# SDP_2.net
KiCad netlist of a schematic drawn in Altium Designer
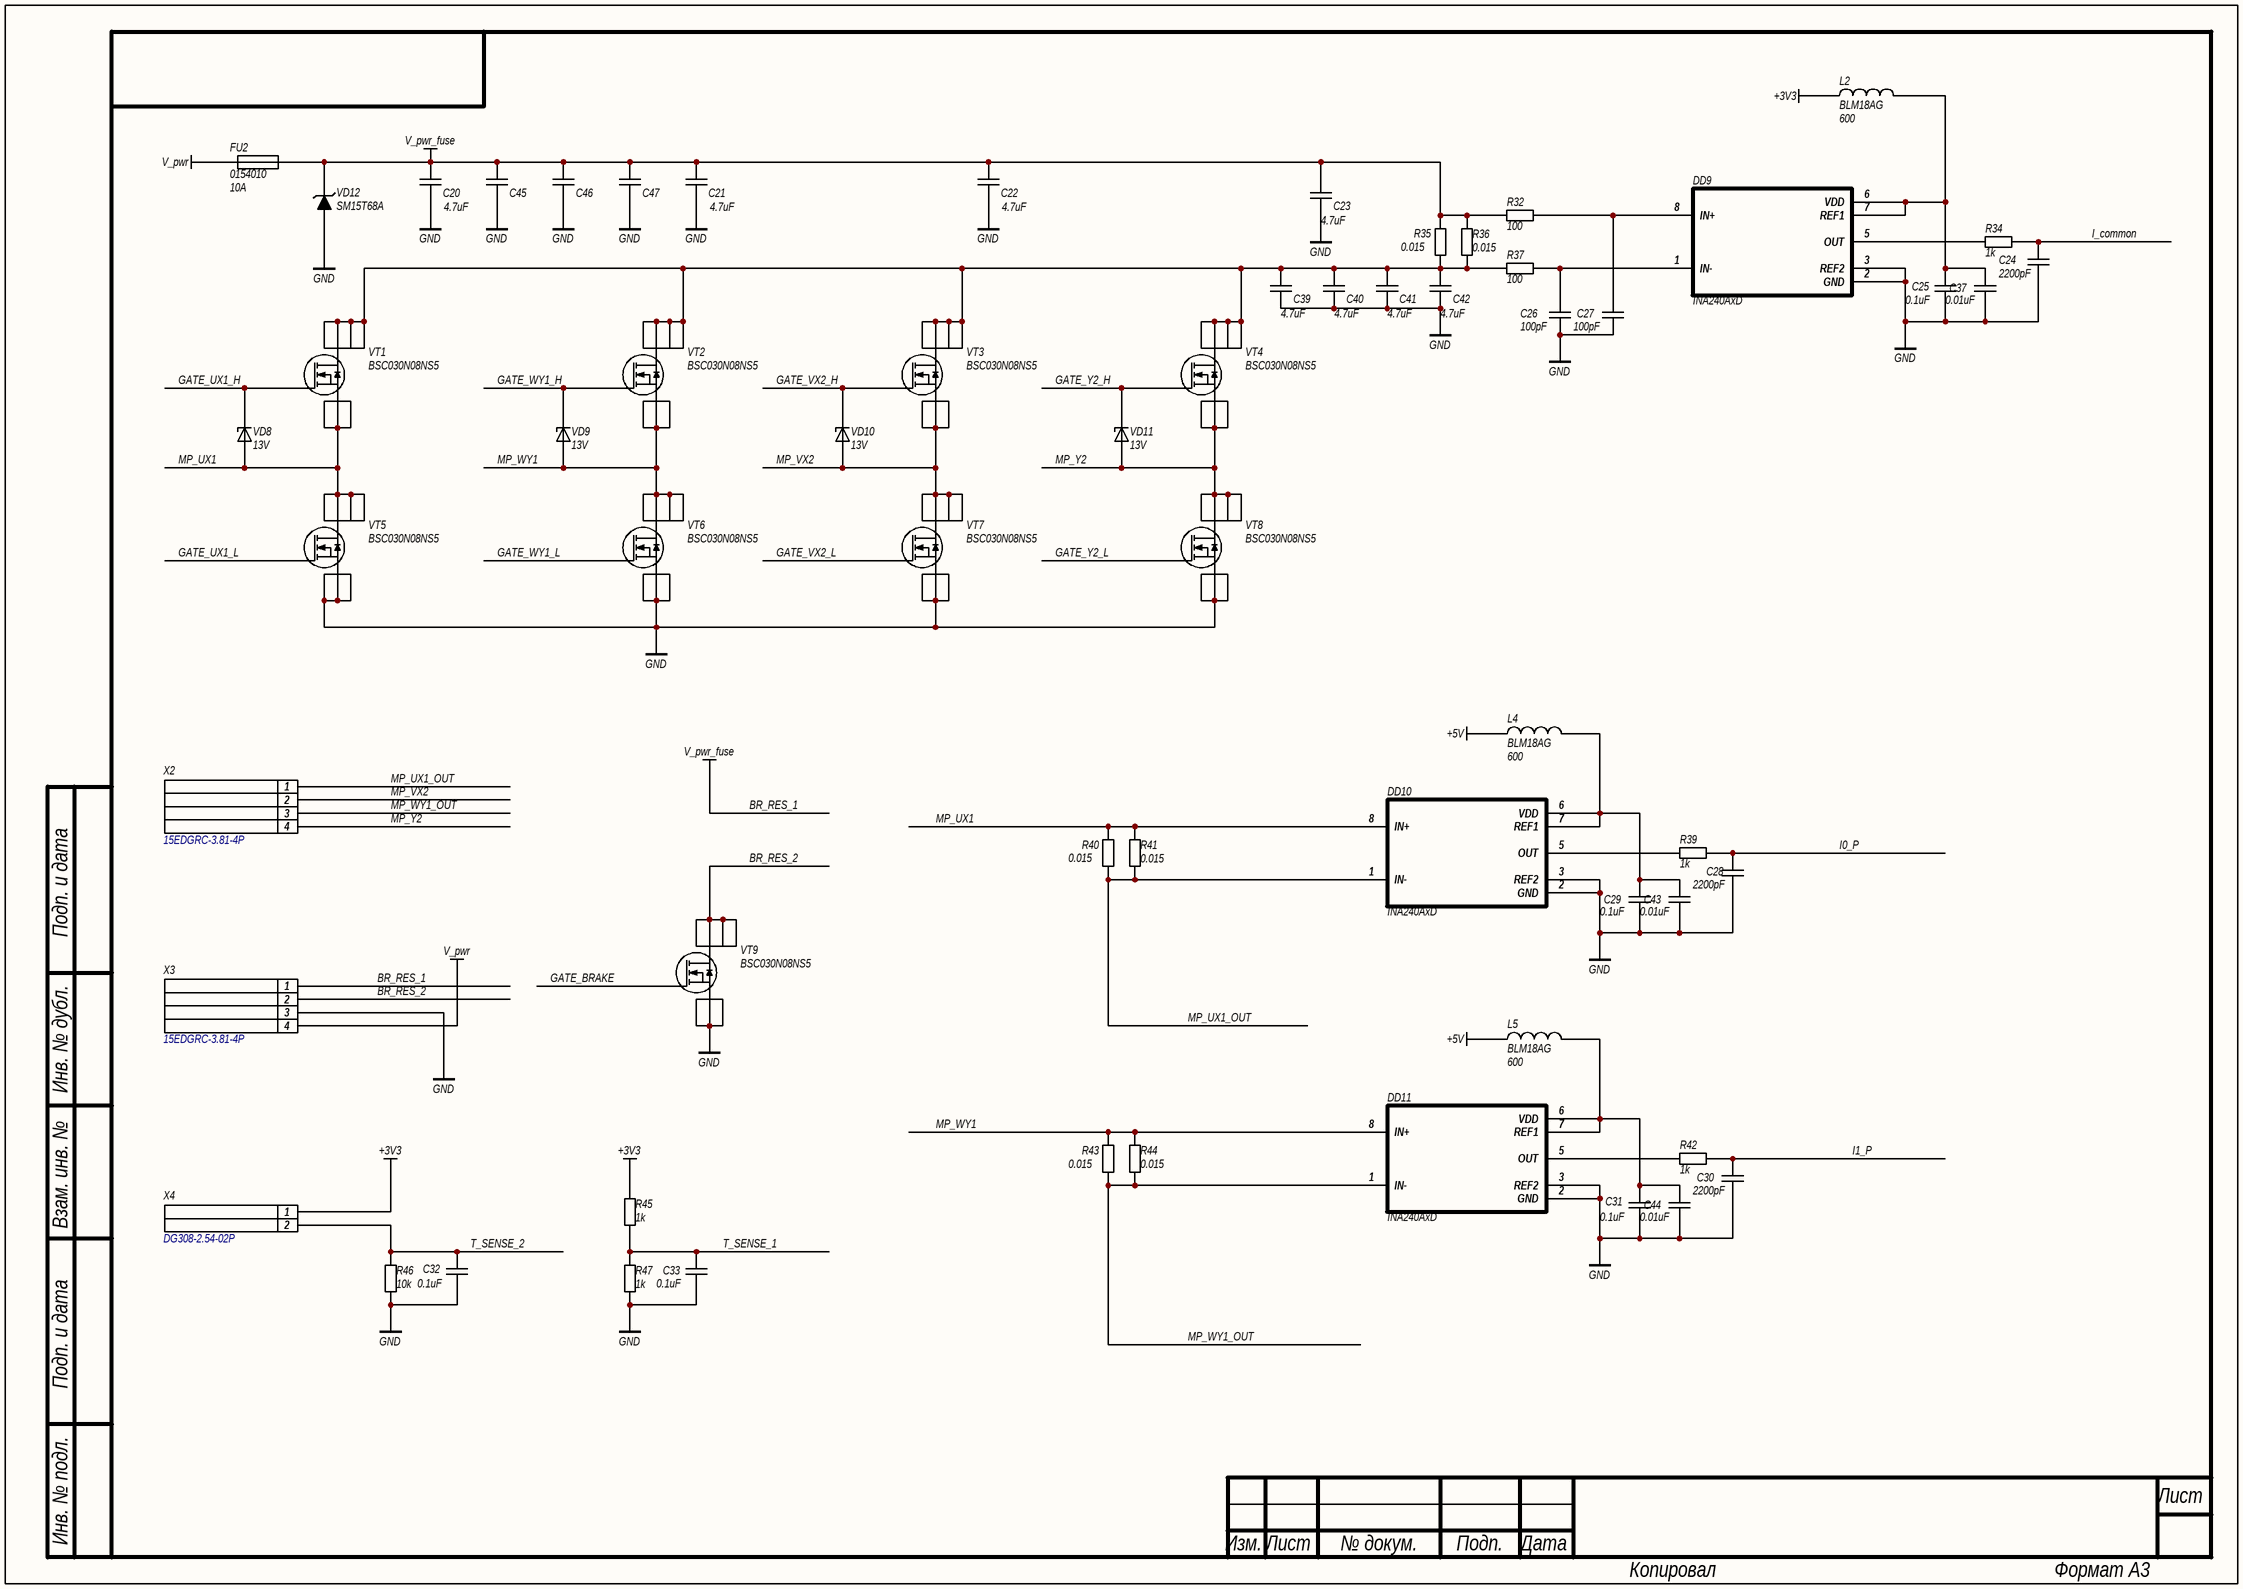
[diagram p0: SDP_2.SchDoc]

(export (version "E")
  (design (tool "Eeschema 10.0.6"))
  (components
    (comp (ref "C20")
      (value "4.7uF")
      (footprint "C1210")
      (description "SMD Capacitor")
      (fields (field (name "MANUFACTURER") "Murata") (field (name "TOLERANCE") "10%"))
      (libsource (lib "VKA") (part "CAP"))
    )
    (comp (ref "C21")
      (value "4.7uF")
      (footprint "C1210")
      (description "SMD Capacitor")
      (fields (field (name "MANUFACTURER") "Murata") (field (name "TOLERANCE") "10%"))
      (libsource (lib "VKA") (part "CAP"))
    )
    (comp (ref "C22")
      (value "4.7uF")
      (footprint "C1210")
      (description "SMD Capacitor")
      (fields (field (name "MANUFACTURER") "Murata") (field (name "TOLERANCE") "10%"))
      (libsource (lib "VKA") (part "CAP"))
    )
    (comp (ref "C23")
      (value "4.7uF")
      (footprint "C1210")
      (description "SMD Capacitor")
      (fields (field (name "MANUFACTURER") "Murata") (field (name "TOLERANCE") "10%"))
      (libsource (lib "VKA") (part "CAP"))
    )
    (comp (ref "C24")
      (value "2200pF")
      (footprint "C0603")
      (description "SMD Capacitor")
      (fields (field (name "MANUFACTURER") "Murata") (field (name "TOLERANCE") "10%"))
      (libsource (lib "VKA") (part "CAP"))
    )
    (comp (ref "C25")
      (value "0.1uF")
      (footprint "C0603")
      (description "SMD Capacitor")
      (fields (field (name "MANUFACTURER") "Murata") (field (name "TOLERANCE") "10%"))
      (libsource (lib "VKA") (part "CAP"))
    )
    (comp (ref "C26")
      (value "100pF")
      (footprint "C0603")
      (description "SMD Capacitor")
      (fields (field (name "MANUFACTURER") "Murata") (field (name "TOLERANCE") "10%"))
      (libsource (lib "VKA") (part "CAP"))
    )
    (comp (ref "C27")
      (value "100pF")
      (footprint "C0603")
      (description "SMD Capacitor")
      (fields (field (name "MANUFACTURER") "Murata") (field (name "TOLERANCE") "10%"))
      (libsource (lib "VKA") (part "CAP"))
    )
    (comp (ref "C28")
      (value "2200pF")
      (footprint "C0603")
      (description "SMD Capacitor")
      (fields (field (name "MANUFACTURER") "Murata") (field (name "TOLERANCE") "10%"))
      (libsource (lib "VKA") (part "CAP"))
    )
    (comp (ref "C29")
      (value "0.1uF")
      (footprint "C0603")
      (description "SMD Capacitor")
      (fields (field (name "MANUFACTURER") "Murata") (field (name "TOLERANCE") "10%"))
      (libsource (lib "VKA") (part "CAP"))
    )
    (comp (ref "C30")
      (value "2200pF")
      (footprint "C0603")
      (description "SMD Capacitor")
      (fields (field (name "MANUFACTURER") "Murata") (field (name "TOLERANCE") "10%"))
      (libsource (lib "VKA") (part "CAP"))
    )
    (comp (ref "C31")
      (value "0.1uF")
      (footprint "C0603")
      (description "SMD Capacitor")
      (fields (field (name "MANUFACTURER") "Murata") (field (name "TOLERANCE") "10%"))
      (libsource (lib "VKA") (part "CAP"))
    )
    (comp (ref "C32")
      (value "0.1uF")
      (footprint "C0603")
      (description "SMD Capacitor")
      (fields (field (name "MANUFACTURER") "Murata") (field (name "TOLERANCE") "10%"))
      (libsource (lib "VKA") (part "CAP"))
    )
    (comp (ref "C33")
      (value "0.1uF")
      (footprint "C0603")
      (description "SMD Capacitor")
      (fields (field (name "MANUFACTURER") "Murata") (field (name "TOLERANCE") "10%"))
      (libsource (lib "VKA") (part "CAP"))
    )
    (comp (ref "C37")
      (value "0.01uF")
      (footprint "C0603")
      (description "SMD Capacitor")
      (fields (field (name "MANUFACTURER") "Murata") (field (name "TOLERANCE") "10%"))
      (libsource (lib "VKA") (part "CAP"))
    )
    (comp (ref "C39")
      (value "4.7uF")
      (footprint "C1210")
      (description "SMD Capacitor")
      (fields (field (name "MANUFACTURER") "Murata") (field (name "TOLERANCE") "10%"))
      (libsource (lib "VKA") (part "CAP"))
    )
    (comp (ref "C40")
      (value "4.7uF")
      (footprint "C1210")
      (description "SMD Capacitor")
      (fields (field (name "MANUFACTURER") "Murata") (field (name "TOLERANCE") "10%"))
      (libsource (lib "VKA") (part "CAP"))
    )
    (comp (ref "C41")
      (value "4.7uF")
      (footprint "C1210")
      (description "SMD Capacitor")
      (fields (field (name "MANUFACTURER") "Murata") (field (name "TOLERANCE") "10%"))
      (libsource (lib "VKA") (part "CAP"))
    )
    (comp (ref "C42")
      (value "4.7uF")
      (footprint "C1210")
      (description "SMD Capacitor")
      (fields (field (name "MANUFACTURER") "Murata") (field (name "TOLERANCE") "10%"))
      (libsource (lib "VKA") (part "CAP"))
    )
    (comp (ref "C43")
      (value "0.01uF")
      (footprint "C0603")
      (description "SMD Capacitor")
      (fields (field (name "MANUFACTURER") "Murata") (field (name "TOLERANCE") "10%"))
      (libsource (lib "VKA") (part "CAP"))
    )
    (comp (ref "C44")
      (value "0.01uF")
      (footprint "C0603")
      (description "SMD Capacitor")
      (fields (field (name "MANUFACTURER") "Murata") (field (name "TOLERANCE") "10%"))
      (libsource (lib "VKA") (part "CAP"))
    )
    (comp (ref "C45")
      (value "CAP")
      (footprint "C2220")
      (description "SMD Capacitor")
      (fields (field (name "MANUFACTURER") "Murata") (field (name "TOLERANCE") "10%"))
      (libsource (lib "VKA") (part "CAP"))
    )
    (comp (ref "C46")
      (value "CAP")
      (footprint "C2220")
      (description "SMD Capacitor")
      (fields (field (name "MANUFACTURER") "Murata") (field (name "TOLERANCE") "10%"))
      (libsource (lib "VKA") (part "CAP"))
    )
    (comp (ref "C47")
      (value "CAP")
      (footprint "C2220")
      (description "SMD Capacitor")
      (fields (field (name "MANUFACTURER") "Murata") (field (name "TOLERANCE") "10%"))
      (libsource (lib "VKA") (part "CAP"))
    )
    (comp (ref "DD9")
      (value "INA240AxD")
      (footprint "SO8_L")
      (description "Current_sesnse_amplifier")
      (libsource (lib "DSP") (part "INA240AxD"))
    )
    (comp (ref "DD10")
      (value "INA240AxD")
      (footprint "SO8_L")
      (description "Current_sesnse_amplifier")
      (libsource (lib "DSP") (part "INA240AxD"))
    )
    (comp (ref "DD11")
      (value "INA240AxD")
      (footprint "SO8_L")
      (description "Current_sesnse_amplifier")
      (libsource (lib "DSP") (part "INA240AxD"))
    )
    (comp (ref "FU2")
      (value "0154010")
      (footprint "omni_block_154")
      (description "omni fuse block")
      (fields (field (name "CURRENT") "10A"))
      (libsource (lib "DSP") (part "0154010"))
    )
    (comp (ref "L2")
      (value "BLM18AG")
      (footprint "R0603")
      (fields (field (name "ALTIUM_VALUE") "600"))
      (libsource (lib "VKA") (part "BLM18AG"))
    )
    (comp (ref "L4")
      (value "BLM18AG")
      (footprint "R0603")
      (fields (field (name "ALTIUM_VALUE") "600"))
      (libsource (lib "VKA") (part "BLM18AG"))
    )
    (comp (ref "L5")
      (value "BLM18AG")
      (footprint "R0603")
      (fields (field (name "ALTIUM_VALUE") "600"))
      (libsource (lib "VKA") (part "BLM18AG"))
    )
    (comp (ref "R32")
      (value "100")
      (footprint "R0603")
      (description "SMD Resistor")
      (fields (field (name "POWER") "0.062 Wt") (field (name "TOLERANCE") "5%"))
      (libsource (lib "") (part "RES_1"))
    )
    (comp (ref "R34")
      (value "1k")
      (footprint "R0603")
      (description "SMD Resistor")
      (fields (field (name "POWER") "0.062 Wt") (field (name "TOLERANCE") "5%"))
      (libsource (lib "") (part "RES_1"))
    )
    (comp (ref "R35")
      (value "0.015")
      (footprint "R2512")
      (description "SMD Resistor")
      (fields (field (name "POWER") "1 W") (field (name "TOLERANCE") "5%"))
      (libsource (lib "VKA") (part "RES2512"))
    )
    (comp (ref "R36")
      (value "0.015")
      (footprint "R2512")
      (description "SMD Resistor")
      (fields (field (name "POWER") "1 W") (field (name "TOLERANCE") "5%"))
      (libsource (lib "VKA") (part "RES2512"))
    )
    (comp (ref "R37")
      (value "100")
      (footprint "R0603")
      (description "SMD Resistor")
      (fields (field (name "POWER") "0.062 Wt") (field (name "TOLERANCE") "5%"))
      (libsource (lib "") (part "RES_1"))
    )
    (comp (ref "R39")
      (value "1k")
      (footprint "R0603")
      (description "SMD Resistor")
      (fields (field (name "POWER") "0.062 Wt") (field (name "TOLERANCE") "5%"))
      (libsource (lib "") (part "RES_1"))
    )
    (comp (ref "R40")
      (value "0.015")
      (footprint "R2512")
      (description "SMD Resistor")
      (fields (field (name "POWER") "1 W") (field (name "TOLERANCE") "5%"))
      (libsource (lib "VKA") (part "RES2512"))
    )
    (comp (ref "R41")
      (value "0.015")
      (footprint "R2512")
      (description "SMD Resistor")
      (fields (field (name "POWER") "1 W") (field (name "TOLERANCE") "5%"))
      (libsource (lib "VKA") (part "RES2512"))
    )
    (comp (ref "R42")
      (value "1k")
      (footprint "R0603")
      (description "SMD Resistor")
      (fields (field (name "POWER") "0.062 Wt") (field (name "TOLERANCE") "5%"))
      (libsource (lib "") (part "RES_1"))
    )
    (comp (ref "R43")
      (value "0.015")
      (footprint "R2512")
      (description "SMD Resistor")
      (fields (field (name "POWER") "1 W") (field (name "TOLERANCE") "5%"))
      (libsource (lib "VKA") (part "RES2512"))
    )
    (comp (ref "R44")
      (value "0.015")
      (footprint "R2512")
      (description "SMD Resistor")
      (fields (field (name "POWER") "1 W") (field (name "TOLERANCE") "5%"))
      (libsource (lib "VKA") (part "RES2512"))
    )
    (comp (ref "R45")
      (value "1k")
      (footprint "R0603")
      (description "SMD Resistor")
      (fields (field (name "POWER") "0.062 Wt") (field (name "TOLERANCE") "5%"))
      (libsource (lib "VKA") (part "RES"))
    )
    (comp (ref "R46")
      (value "10k")
      (footprint "R0603")
      (description "SMD Resistor")
      (fields (field (name "POWER") "0.062 Wt") (field (name "TOLERANCE") "5%"))
      (libsource (lib "VKA") (part "RES"))
    )
    (comp (ref "R47")
      (value "1k")
      (footprint "R0603")
      (description "SMD Resistor")
      (fields (field (name "POWER") "0.062 Wt") (field (name "TOLERANCE") "5%"))
      (libsource (lib "VKA") (part "RES"))
    )
    (comp (ref "VD8")
      (value "BZX384")
      (footprint "SOD323")
      (fields (field (name "VOLTAGE") "13V"))
      (libsource (lib "VKA") (part "BZX384"))
    )
    (comp (ref "VD9")
      (value "BZX384")
      (footprint "SOD323")
      (fields (field (name "VOLTAGE") "13V"))
      (libsource (lib "VKA") (part "BZX384"))
    )
    (comp (ref "VD10")
      (value "BZX384")
      (footprint "SOD323")
      (fields (field (name "VOLTAGE") "13V"))
      (libsource (lib "VKA") (part "BZX384"))
    )
    (comp (ref "VD11")
      (value "BZX384")
      (footprint "SOD323")
      (fields (field (name "VOLTAGE") "13V"))
      (libsource (lib "VKA") (part "BZX384"))
    )
    (comp (ref "VD12")
      (value "SM15T68A")
      (footprint "SMC-DO214")
      (description "TVSdiode")
      (libsource (lib "VKA") (part "SM15T68A"))
    )
    (comp (ref "VT1")
      (value "BSC030N08NS5")
      (footprint "TDSON-8")
      (description "MOSFET-N")
      (libsource (lib "DSP") (part "BSC030N08NS5"))
    )
    (comp (ref "VT2")
      (value "BSC030N08NS5")
      (footprint "TDSON-8")
      (description "MOSFET-N")
      (libsource (lib "DSP") (part "BSC030N08NS5"))
    )
    (comp (ref "VT3")
      (value "BSC030N08NS5")
      (footprint "TDSON-8")
      (description "MOSFET-N")
      (libsource (lib "DSP") (part "BSC030N08NS5"))
    )
    (comp (ref "VT4")
      (value "BSC030N08NS5")
      (footprint "TDSON-8")
      (description "MOSFET-N")
      (libsource (lib "DSP") (part "BSC030N08NS5"))
    )
    (comp (ref "VT5")
      (value "BSC030N08NS5")
      (footprint "TDSON-8")
      (description "MOSFET-N")
      (libsource (lib "DSP") (part "BSC030N08NS5"))
    )
    (comp (ref "VT6")
      (value "BSC030N08NS5")
      (footprint "TDSON-8")
      (description "MOSFET-N")
      (libsource (lib "DSP") (part "BSC030N08NS5"))
    )
    (comp (ref "VT7")
      (value "BSC030N08NS5")
      (footprint "TDSON-8")
      (description "MOSFET-N")
      (libsource (lib "DSP") (part "BSC030N08NS5"))
    )
    (comp (ref "VT8")
      (value "BSC030N08NS5")
      (footprint "TDSON-8")
      (description "MOSFET-N")
      (libsource (lib "DSP") (part "BSC030N08NS5"))
    )
    (comp (ref "VT9")
      (value "BSC030N08NS5")
      (footprint "TDSON-8")
      (description "MOSFET-N")
      (libsource (lib "DSP") (part "BSC030N08NS5"))
    )
    (comp (ref "X2")
      (value "15EDGRC-3.81-4P")
      (footprint "15EDGRC")
      (libsource (lib "DSP") (part "15EDGRC-3.81-4P"))
    )
    (comp (ref "X3")
      (value "15EDGRC-3.81-4P")
      (footprint "15EDGRC")
      (libsource (lib "DSP") (part "15EDGRC-3.81-4P"))
    )
    (comp (ref "X4")
      (value "DG308-2.54-02P")
      (footprint "DG308-2.54-2")
      (libsource (lib "DSP") (part "DG308-2.54-02P"))
    )
  )
  (nets
    (net (code "1") (name "+3V3") (class "Default")
      (node (ref "L2") (pin "1") (pinfunction "1_1") (pintype "passive"))
      (node (ref "R45") (pin "2") (pinfunction "2_2") (pintype "passive"))
      (node (ref "X4") (pin "1") (pinfunction "1_1") (pintype "passive"))
    )
    (net (code "2") (name "+5V") (class "Default")
      (node (ref "L4") (pin "1") (pinfunction "1_1") (pintype "passive"))
      (node (ref "L5") (pin "1") (pinfunction "1_1") (pintype "passive"))
    )
    (net (code "3") (name "/BR_RES_2") (class "Default")
      (node (ref "VT9") (pin "5") (pinfunction "D_5") (pintype "passive"))
      (node (ref "VT9") (pin "6") (pinfunction "D_6") (pintype "passive"))
      (node (ref "VT9") (pin "7") (pinfunction "D_7") (pintype "passive"))
      (node (ref "VT9") (pin "8") (pinfunction "D_8") (pintype "passive"))
      (node (ref "X3") (pin "2") (pinfunction "2_2") (pintype "passive"))
    )
    (net (code "4") (name "/GATE_BRAKE") (class "Default")
      (node (ref "VT9") (pin "4") (pinfunction "G_4") (pintype "passive"))
    )
    (net (code "5") (name "/GATE_UX1_H") (class "Default")
      (node (ref "VD8") (pin "2") (pinfunction "K_2") (pintype "passive"))
      (node (ref "VT1") (pin "4") (pinfunction "G_4") (pintype "passive"))
    )
    (net (code "6") (name "/GATE_UX1_L") (class "Default")
      (node (ref "VT5") (pin "4") (pinfunction "G_4") (pintype "passive"))
    )
    (net (code "7") (name "/GATE_VX2_H") (class "Default")
      (node (ref "VD10") (pin "2") (pinfunction "K_2") (pintype "passive"))
      (node (ref "VT3") (pin "4") (pinfunction "G_4") (pintype "passive"))
    )
    (net (code "8") (name "/GATE_VX2_L") (class "Default")
      (node (ref "VT7") (pin "4") (pinfunction "G_4") (pintype "passive"))
    )
    (net (code "9") (name "/GATE_WY1_H") (class "Default")
      (node (ref "VD9") (pin "2") (pinfunction "K_2") (pintype "passive"))
      (node (ref "VT2") (pin "4") (pinfunction "G_4") (pintype "passive"))
    )
    (net (code "10") (name "/GATE_WY1_L") (class "Default")
      (node (ref "VT6") (pin "4") (pinfunction "G_4") (pintype "passive"))
    )
    (net (code "11") (name "/GATE_Y2_H") (class "Default")
      (node (ref "VD11") (pin "2") (pinfunction "K_2") (pintype "passive"))
      (node (ref "VT4") (pin "4") (pinfunction "G_4") (pintype "passive"))
    )
    (net (code "12") (name "/GATE_Y2_L") (class "Default")
      (node (ref "VT8") (pin "4") (pinfunction "G_4") (pintype "passive"))
    )
    (net (code "13") (name "/I0_P") (class "Default")
      (node (ref "C28") (pin "2") (pinfunction "2_2") (pintype "passive"))
      (node (ref "R39") (pin "2") (pinfunction "2_2") (pintype "passive"))
    )
    (net (code "14") (name "/I1_P") (class "Default")
      (node (ref "C30") (pin "2") (pinfunction "2_2") (pintype "passive"))
      (node (ref "R42") (pin "2") (pinfunction "2_2") (pintype "passive"))
    )
    (net (code "15") (name "/I_common") (class "Default")
      (node (ref "C24") (pin "2") (pinfunction "2_2") (pintype "passive"))
      (node (ref "R34") (pin "2") (pinfunction "2_2") (pintype "passive"))
    )
    (net (code "16") (name "/MP_UX1") (class "Default")
      (node (ref "DD10") (pin "8") (pinfunction "IN+_8") (pintype "passive"))
      (node (ref "R40") (pin "2") (pinfunction "2_2") (pintype "passive"))
      (node (ref "R41") (pin "2") (pinfunction "2_2") (pintype "passive"))
      (node (ref "VD8") (pin "1") (pinfunction "A_1") (pintype "passive"))
      (node (ref "VT1") (pin "1") (pinfunction "S_1") (pintype "passive"))
      (node (ref "VT1") (pin "2") (pinfunction "S_2") (pintype "passive"))
      (node (ref "VT1") (pin "3") (pinfunction "S_3") (pintype "passive"))
      (node (ref "VT5") (pin "5") (pinfunction "D_5") (pintype "passive"))
      (node (ref "VT5") (pin "6") (pinfunction "D_6") (pintype "passive"))
      (node (ref "VT5") (pin "7") (pinfunction "D_7") (pintype "passive"))
      (node (ref "VT5") (pin "8") (pinfunction "D_8") (pintype "passive"))
    )
    (net (code "17") (name "/MP_UX1_OUT") (class "Default")
      (node (ref "DD10") (pin "1") (pinfunction "IN-_1") (pintype "passive"))
      (node (ref "R40") (pin "1") (pinfunction "1_1") (pintype "passive"))
      (node (ref "R41") (pin "1") (pinfunction "1_1") (pintype "passive"))
      (node (ref "X2") (pin "1") (pinfunction "1_1") (pintype "passive"))
    )
    (net (code "18") (name "/MP_VX2") (class "Default")
      (node (ref "VD10") (pin "1") (pinfunction "A_1") (pintype "passive"))
      (node (ref "VT3") (pin "1") (pinfunction "S_1") (pintype "passive"))
      (node (ref "VT3") (pin "2") (pinfunction "S_2") (pintype "passive"))
      (node (ref "VT3") (pin "3") (pinfunction "S_3") (pintype "passive"))
      (node (ref "VT7") (pin "5") (pinfunction "D_5") (pintype "passive"))
      (node (ref "VT7") (pin "6") (pinfunction "D_6") (pintype "passive"))
      (node (ref "VT7") (pin "7") (pinfunction "D_7") (pintype "passive"))
      (node (ref "VT7") (pin "8") (pinfunction "D_8") (pintype "passive"))
      (node (ref "X2") (pin "2") (pinfunction "2_2") (pintype "passive"))
    )
    (net (code "19") (name "/MP_WY1") (class "Default")
      (node (ref "DD11") (pin "8") (pinfunction "IN+_8") (pintype "passive"))
      (node (ref "R43") (pin "2") (pinfunction "2_2") (pintype "passive"))
      (node (ref "R44") (pin "2") (pinfunction "2_2") (pintype "passive"))
      (node (ref "VD9") (pin "1") (pinfunction "A_1") (pintype "passive"))
      (node (ref "VT2") (pin "1") (pinfunction "S_1") (pintype "passive"))
      (node (ref "VT2") (pin "2") (pinfunction "S_2") (pintype "passive"))
      (node (ref "VT2") (pin "3") (pinfunction "S_3") (pintype "passive"))
      (node (ref "VT6") (pin "5") (pinfunction "D_5") (pintype "passive"))
      (node (ref "VT6") (pin "6") (pinfunction "D_6") (pintype "passive"))
      (node (ref "VT6") (pin "7") (pinfunction "D_7") (pintype "passive"))
      (node (ref "VT6") (pin "8") (pinfunction "D_8") (pintype "passive"))
    )
    (net (code "20") (name "/MP_WY1_OUT") (class "Default")
      (node (ref "DD11") (pin "1") (pinfunction "IN-_1") (pintype "passive"))
      (node (ref "R43") (pin "1") (pinfunction "1_1") (pintype "passive"))
      (node (ref "R44") (pin "1") (pinfunction "1_1") (pintype "passive"))
      (node (ref "X2") (pin "3") (pinfunction "3_3") (pintype "passive"))
    )
    (net (code "21") (name "/MP_Y2") (class "Default")
      (node (ref "VD11") (pin "1") (pinfunction "A_1") (pintype "passive"))
      (node (ref "VT4") (pin "1") (pinfunction "S_1") (pintype "passive"))
      (node (ref "VT4") (pin "2") (pinfunction "S_2") (pintype "passive"))
      (node (ref "VT4") (pin "3") (pinfunction "S_3") (pintype "passive"))
      (node (ref "VT8") (pin "5") (pinfunction "D_5") (pintype "passive"))
      (node (ref "VT8") (pin "6") (pinfunction "D_6") (pintype "passive"))
      (node (ref "VT8") (pin "7") (pinfunction "D_7") (pintype "passive"))
      (node (ref "VT8") (pin "8") (pinfunction "D_8") (pintype "passive"))
      (node (ref "X2") (pin "4") (pinfunction "4_4") (pintype "passive"))
    )
    (net (code "22") (name "/T_SENSE_1") (class "Default")
      (node (ref "C33") (pin "2") (pinfunction "2_2") (pintype "passive"))
      (node (ref "R45") (pin "1") (pinfunction "1_1") (pintype "passive"))
      (node (ref "R47") (pin "2") (pinfunction "2_2") (pintype "passive"))
    )
    (net (code "23") (name "/T_SENSE_2") (class "Default")
      (node (ref "C32") (pin "2") (pinfunction "2_2") (pintype "passive"))
      (node (ref "R46") (pin "2") (pinfunction "2_2") (pintype "passive"))
      (node (ref "X4") (pin "2") (pinfunction "2_2") (pintype "passive"))
    )
    (net (code "24") (name "GND") (class "Default")
      (node (ref "C20") (pin "1") (pinfunction "1_1") (pintype "passive"))
      (node (ref "C21") (pin "1") (pinfunction "1_1") (pintype "passive"))
      (node (ref "C22") (pin "1") (pinfunction "1_1") (pintype "passive"))
      (node (ref "C23") (pin "1") (pinfunction "1_1") (pintype "passive"))
      (node (ref "C24") (pin "1") (pinfunction "1_1") (pintype "passive"))
      (node (ref "C25") (pin "1") (pinfunction "1_1") (pintype "passive"))
      (node (ref "C26") (pin "1") (pinfunction "1_1") (pintype "passive"))
      (node (ref "C27") (pin "1") (pinfunction "1_1") (pintype "passive"))
      (node (ref "C28") (pin "1") (pinfunction "1_1") (pintype "passive"))
      (node (ref "C29") (pin "1") (pinfunction "1_1") (pintype "passive"))
      (node (ref "C30") (pin "1") (pinfunction "1_1") (pintype "passive"))
      (node (ref "C31") (pin "1") (pinfunction "1_1") (pintype "passive"))
      (node (ref "C32") (pin "1") (pinfunction "1_1") (pintype "passive"))
      (node (ref "C33") (pin "1") (pinfunction "1_1") (pintype "passive"))
      (node (ref "C37") (pin "1") (pinfunction "1_1") (pintype "passive"))
      (node (ref "C39") (pin "1") (pinfunction "1_1") (pintype "passive"))
      (node (ref "C40") (pin "1") (pinfunction "1_1") (pintype "passive"))
      (node (ref "C41") (pin "1") (pinfunction "1_1") (pintype "passive"))
      (node (ref "C42") (pin "1") (pinfunction "1_1") (pintype "passive"))
      (node (ref "C43") (pin "1") (pinfunction "1_1") (pintype "passive"))
      (node (ref "C44") (pin "1") (pinfunction "1_1") (pintype "passive"))
      (node (ref "C45") (pin "1") (pinfunction "1_1") (pintype "passive"))
      (node (ref "C46") (pin "1") (pinfunction "1_1") (pintype "passive"))
      (node (ref "C47") (pin "1") (pinfunction "1_1") (pintype "passive"))
      (node (ref "DD10") (pin "2") (pinfunction "GND_2") (pintype "passive"))
      (node (ref "DD10") (pin "3") (pinfunction "REF2_3") (pintype "passive"))
      (node (ref "DD11") (pin "2") (pinfunction "GND_2") (pintype "passive"))
      (node (ref "DD11") (pin "3") (pinfunction "REF2_3") (pintype "passive"))
      (node (ref "DD9") (pin "2") (pinfunction "GND_2") (pintype "passive"))
      (node (ref "DD9") (pin "3") (pinfunction "REF2_3") (pintype "passive"))
      (node (ref "R46") (pin "1") (pinfunction "1_1") (pintype "passive"))
      (node (ref "R47") (pin "1") (pinfunction "1_1") (pintype "passive"))
      (node (ref "VD12") (pin "1") (pinfunction "A_1") (pintype "passive"))
      (node (ref "VT5") (pin "1") (pinfunction "S_1") (pintype "passive"))
      (node (ref "VT5") (pin "2") (pinfunction "S_2") (pintype "passive"))
      (node (ref "VT5") (pin "3") (pinfunction "S_3") (pintype "passive"))
      (node (ref "VT6") (pin "1") (pinfunction "S_1") (pintype "passive"))
      (node (ref "VT6") (pin "2") (pinfunction "S_2") (pintype "passive"))
      (node (ref "VT6") (pin "3") (pinfunction "S_3") (pintype "passive"))
      (node (ref "VT7") (pin "1") (pinfunction "S_1") (pintype "passive"))
      (node (ref "VT7") (pin "2") (pinfunction "S_2") (pintype "passive"))
      (node (ref "VT7") (pin "3") (pinfunction "S_3") (pintype "passive"))
      (node (ref "VT8") (pin "1") (pinfunction "S_1") (pintype "passive"))
      (node (ref "VT8") (pin "2") (pinfunction "S_2") (pintype "passive"))
      (node (ref "VT8") (pin "3") (pinfunction "S_3") (pintype "passive"))
      (node (ref "VT9") (pin "1") (pinfunction "S_1") (pintype "passive"))
      (node (ref "VT9") (pin "2") (pinfunction "S_2") (pintype "passive"))
      (node (ref "VT9") (pin "3") (pinfunction "S_3") (pintype "passive"))
      (node (ref "X3") (pin "3") (pinfunction "3_3") (pintype "passive"))
    )
    (net (code "25") (name "Net-(C39-Pad2)") (class "Default")
      (node (ref "C39") (pin "2") (pinfunction "2_2") (pintype "passive"))
      (node (ref "C40") (pin "2") (pinfunction "2_2") (pintype "passive"))
      (node (ref "C41") (pin "2") (pinfunction "2_2") (pintype "passive"))
      (node (ref "C42") (pin "2") (pinfunction "2_2") (pintype "passive"))
      (node (ref "R35") (pin "1") (pinfunction "1_1") (pintype "passive"))
      (node (ref "R36") (pin "1") (pinfunction "1_1") (pintype "passive"))
      (node (ref "R37") (pin "1") (pinfunction "1_1") (pintype "passive"))
      (node (ref "VT1") (pin "5") (pinfunction "D_5") (pintype "passive"))
      (node (ref "VT1") (pin "6") (pinfunction "D_6") (pintype "passive"))
      (node (ref "VT1") (pin "7") (pinfunction "D_7") (pintype "passive"))
      (node (ref "VT1") (pin "8") (pinfunction "D_8") (pintype "passive"))
      (node (ref "VT2") (pin "5") (pinfunction "D_5") (pintype "passive"))
      (node (ref "VT2") (pin "6") (pinfunction "D_6") (pintype "passive"))
      (node (ref "VT2") (pin "7") (pinfunction "D_7") (pintype "passive"))
      (node (ref "VT2") (pin "8") (pinfunction "D_8") (pintype "passive"))
      (node (ref "VT3") (pin "5") (pinfunction "D_5") (pintype "passive"))
      (node (ref "VT3") (pin "6") (pinfunction "D_6") (pintype "passive"))
      (node (ref "VT3") (pin "7") (pinfunction "D_7") (pintype "passive"))
      (node (ref "VT3") (pin "8") (pinfunction "D_8") (pintype "passive"))
      (node (ref "VT4") (pin "5") (pinfunction "D_5") (pintype "passive"))
      (node (ref "VT4") (pin "6") (pinfunction "D_6") (pintype "passive"))
      (node (ref "VT4") (pin "7") (pinfunction "D_7") (pintype "passive"))
      (node (ref "VT4") (pin "8") (pinfunction "D_8") (pintype "passive"))
    )
    (net (code "26") (name "Net-(DD9-IN+)") (class "Default")
      (node (ref "C27") (pin "2") (pinfunction "2_2") (pintype "passive"))
      (node (ref "DD9") (pin "8") (pinfunction "IN+_8") (pintype "passive"))
      (node (ref "R32") (pin "2") (pinfunction "2_2") (pintype "passive"))
    )
    (net (code "27") (name "Net-(DD9-IN-)") (class "Default")
      (node (ref "C26") (pin "2") (pinfunction "2_2") (pintype "passive"))
      (node (ref "DD9") (pin "1") (pinfunction "IN-_1") (pintype "passive"))
      (node (ref "R37") (pin "2") (pinfunction "2_2") (pintype "passive"))
    )
    (net (code "28") (name "Net-(DD9-OUT)") (class "Default")
      (node (ref "DD9") (pin "5") (pinfunction "OUT_5") (pintype "passive"))
      (node (ref "R34") (pin "1") (pinfunction "1_1") (pintype "passive"))
    )
    (net (code "29") (name "Net-(DD9-REF1)") (class "Default")
      (node (ref "C25") (pin "2") (pinfunction "2_2") (pintype "passive"))
      (node (ref "C37") (pin "2") (pinfunction "2_2") (pintype "passive"))
      (node (ref "DD9") (pin "6") (pinfunction "VDD_6") (pintype "passive"))
      (node (ref "DD9") (pin "7") (pinfunction "REF1_7") (pintype "passive"))
      (node (ref "L2") (pin "2") (pinfunction "2_2") (pintype "passive"))
    )
    (net (code "30") (name "Net-(DD10-OUT)") (class "Default")
      (node (ref "DD10") (pin "5") (pinfunction "OUT_5") (pintype "passive"))
      (node (ref "R39") (pin "1") (pinfunction "1_1") (pintype "passive"))
    )
    (net (code "31") (name "Net-(DD10-REF1)") (class "Default")
      (node (ref "C29") (pin "2") (pinfunction "2_2") (pintype "passive"))
      (node (ref "C43") (pin "2") (pinfunction "2_2") (pintype "passive"))
      (node (ref "DD10") (pin "6") (pinfunction "VDD_6") (pintype "passive"))
      (node (ref "DD10") (pin "7") (pinfunction "REF1_7") (pintype "passive"))
      (node (ref "L4") (pin "2") (pinfunction "2_2") (pintype "passive"))
    )
    (net (code "32") (name "Net-(DD11-OUT)") (class "Default")
      (node (ref "DD11") (pin "5") (pinfunction "OUT_5") (pintype "passive"))
      (node (ref "R42") (pin "1") (pinfunction "1_1") (pintype "passive"))
    )
    (net (code "33") (name "Net-(DD11-REF1)") (class "Default")
      (node (ref "C31") (pin "2") (pinfunction "2_2") (pintype "passive"))
      (node (ref "C44") (pin "2") (pinfunction "2_2") (pintype "passive"))
      (node (ref "DD11") (pin "6") (pinfunction "VDD_6") (pintype "passive"))
      (node (ref "DD11") (pin "7") (pinfunction "REF1_7") (pintype "passive"))
      (node (ref "L5") (pin "2") (pinfunction "2_2") (pintype "passive"))
    )
    (net (code "34") (name "V_pwr") (class "Default")
      (node (ref "FU2") (pin "1") (pinfunction "1_1") (pintype "passive"))
      (node (ref "X3") (pin "4") (pinfunction "4_4") (pintype "passive"))
    )
    (net (code "35") (name "V_pwr_fuse") (class "Default")
      (node (ref "C20") (pin "2") (pinfunction "2_2") (pintype "passive"))
      (node (ref "C21") (pin "2") (pinfunction "2_2") (pintype "passive"))
      (node (ref "C22") (pin "2") (pinfunction "2_2") (pintype "passive"))
      (node (ref "C23") (pin "2") (pinfunction "2_2") (pintype "passive"))
      (node (ref "C45") (pin "2") (pinfunction "2_2") (pintype "passive"))
      (node (ref "C46") (pin "2") (pinfunction "2_2") (pintype "passive"))
      (node (ref "C47") (pin "2") (pinfunction "2_2") (pintype "passive"))
      (node (ref "FU2") (pin "2") (pinfunction "2_2") (pintype "passive"))
      (node (ref "R32") (pin "1") (pinfunction "1_1") (pintype "passive"))
      (node (ref "R35") (pin "2") (pinfunction "2_2") (pintype "passive"))
      (node (ref "R36") (pin "2") (pinfunction "2_2") (pintype "passive"))
      (node (ref "VD12") (pin "2") (pinfunction "B_2") (pintype "passive"))
      (node (ref "X3") (pin "1") (pinfunction "1_1") (pintype "passive"))
    )
  )
)
